# GPACConnector.net
KiCad netlist of a schematic drawn in Altium Designer
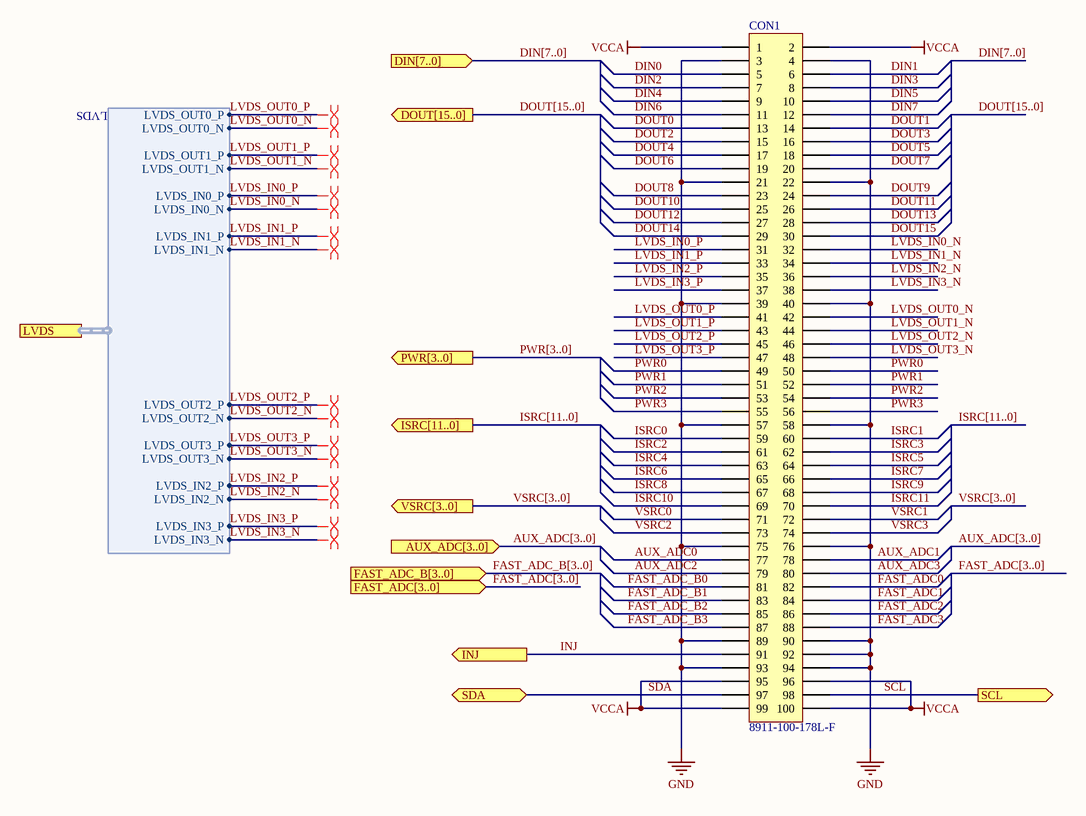
[diagram p0: GPACConnector.SchDoc]

(export (version "E")
  (design (tool "Eeschema 10.0.6"))
  (components
    (comp (ref "CON1")
      (value "-")
      (footprint "KEL 8911-100-178L-F, PLUG")
      (description "KEL 8911 100 pin board to board connector")
      (fields (field (name "TYPE_1") "8911-100-178L-F") (field (name "PUBLISHER") "Silab J.S."))
      (libsource (lib "Silab_Lib") (part "CON KEL 8911, male"))
    )
  )
  (nets
    (net (code "2") (name "/AUX_ADC0") (class "Default")
      (node (ref "CON1") (pin "77") (pinfunction "77_77") (pintype "passive"))
    )
    (net (code "3") (name "/AUX_ADC1") (class "Default")
      (node (ref "CON1") (pin "78") (pinfunction "78_78") (pintype "passive"))
    )
    (net (code "4") (name "/AUX_ADC2") (class "Default")
      (node (ref "CON1") (pin "79") (pinfunction "79_79") (pintype "passive"))
    )
    (net (code "5") (name "/AUX_ADC3") (class "Default")
      (node (ref "CON1") (pin "80") (pinfunction "80_80") (pintype "passive"))
    )
    (net (code "7") (name "/DIN0") (class "Default")
      (node (ref "CON1") (pin "5") (pinfunction "5_5") (pintype "passive"))
    )
    (net (code "8") (name "/DIN1") (class "Default")
      (node (ref "CON1") (pin "6") (pinfunction "6_6") (pintype "passive"))
    )
    (net (code "9") (name "/DIN2") (class "Default")
      (node (ref "CON1") (pin "7") (pinfunction "7_7") (pintype "passive"))
    )
    (net (code "10") (name "/DIN3") (class "Default")
      (node (ref "CON1") (pin "8") (pinfunction "8_8") (pintype "passive"))
    )
    (net (code "11") (name "/DIN4") (class "Default")
      (node (ref "CON1") (pin "9") (pinfunction "9_9") (pintype "passive"))
    )
    (net (code "12") (name "/DIN5") (class "Default")
      (node (ref "CON1") (pin "10") (pinfunction "10_10") (pintype "passive"))
    )
    (net (code "13") (name "/DIN6") (class "Default")
      (node (ref "CON1") (pin "11") (pinfunction "11_11") (pintype "passive"))
    )
    (net (code "14") (name "/DIN7") (class "Default")
      (node (ref "CON1") (pin "12") (pinfunction "12_12") (pintype "passive"))
    )
    (net (code "16") (name "/DOUT0") (class "Default")
      (node (ref "CON1") (pin "13") (pinfunction "13_13") (pintype "passive"))
    )
    (net (code "17") (name "/DOUT1") (class "Default")
      (node (ref "CON1") (pin "14") (pinfunction "14_14") (pintype "passive"))
    )
    (net (code "18") (name "/DOUT2") (class "Default")
      (node (ref "CON1") (pin "15") (pinfunction "15_15") (pintype "passive"))
    )
    (net (code "19") (name "/DOUT3") (class "Default")
      (node (ref "CON1") (pin "16") (pinfunction "16_16") (pintype "passive"))
    )
    (net (code "20") (name "/DOUT4") (class "Default")
      (node (ref "CON1") (pin "17") (pinfunction "17_17") (pintype "passive"))
    )
    (net (code "21") (name "/DOUT5") (class "Default")
      (node (ref "CON1") (pin "18") (pinfunction "18_18") (pintype "passive"))
    )
    (net (code "22") (name "/DOUT6") (class "Default")
      (node (ref "CON1") (pin "19") (pinfunction "19_19") (pintype "passive"))
    )
    (net (code "23") (name "/DOUT7") (class "Default")
      (node (ref "CON1") (pin "20") (pinfunction "20_20") (pintype "passive"))
    )
    (net (code "24") (name "/DOUT8") (class "Default")
      (node (ref "CON1") (pin "23") (pinfunction "23_23") (pintype "passive"))
    )
    (net (code "25") (name "/DOUT9") (class "Default")
      (node (ref "CON1") (pin "24") (pinfunction "24_24") (pintype "passive"))
    )
    (net (code "26") (name "/DOUT10") (class "Default")
      (node (ref "CON1") (pin "25") (pinfunction "25_25") (pintype "passive"))
    )
    (net (code "27") (name "/DOUT11") (class "Default")
      (node (ref "CON1") (pin "26") (pinfunction "26_26") (pintype "passive"))
    )
    (net (code "28") (name "/DOUT12") (class "Default")
      (node (ref "CON1") (pin "27") (pinfunction "27_27") (pintype "passive"))
    )
    (net (code "29") (name "/DOUT13") (class "Default")
      (node (ref "CON1") (pin "28") (pinfunction "28_28") (pintype "passive"))
    )
    (net (code "30") (name "/DOUT14") (class "Default")
      (node (ref "CON1") (pin "29") (pinfunction "29_29") (pintype "passive"))
    )
    (net (code "31") (name "/DOUT15") (class "Default")
      (node (ref "CON1") (pin "30") (pinfunction "30_30") (pintype "passive"))
    )
    (net (code "33") (name "/FAST_ADC0") (class "Default")
      (node (ref "CON1") (pin "82") (pinfunction "82_82") (pintype "passive"))
    )
    (net (code "34") (name "/FAST_ADC1") (class "Default")
      (node (ref "CON1") (pin "84") (pinfunction "84_84") (pintype "passive"))
    )
    (net (code "35") (name "/FAST_ADC2") (class "Default")
      (node (ref "CON1") (pin "86") (pinfunction "86_86") (pintype "passive"))
    )
    (net (code "36") (name "/FAST_ADC3") (class "Default")
      (node (ref "CON1") (pin "88") (pinfunction "88_88") (pintype "passive"))
    )
    (net (code "38") (name "/FAST_ADC_B0") (class "Default")
      (node (ref "CON1") (pin "81") (pinfunction "81_81") (pintype "passive"))
    )
    (net (code "39") (name "/FAST_ADC_B1") (class "Default")
      (node (ref "CON1") (pin "83") (pinfunction "83_83") (pintype "passive"))
    )
    (net (code "40") (name "/FAST_ADC_B2") (class "Default")
      (node (ref "CON1") (pin "85") (pinfunction "85_85") (pintype "passive"))
    )
    (net (code "41") (name "/FAST_ADC_B3") (class "Default")
      (node (ref "CON1") (pin "87") (pinfunction "87_87") (pintype "passive"))
    )
    (net (code "43") (name "/INJ") (class "Default")
      (node (ref "CON1") (pin "91") (pinfunction "91_91") (pintype "passive"))
    )
    (net (code "44") (name "/ISRC0") (class "Default")
      (node (ref "CON1") (pin "59") (pinfunction "59_59") (pintype "passive"))
    )
    (net (code "45") (name "/ISRC1") (class "Default")
      (node (ref "CON1") (pin "60") (pinfunction "60_60") (pintype "passive"))
    )
    (net (code "46") (name "/ISRC2") (class "Default")
      (node (ref "CON1") (pin "61") (pinfunction "61_61") (pintype "passive"))
    )
    (net (code "47") (name "/ISRC3") (class "Default")
      (node (ref "CON1") (pin "62") (pinfunction "62_62") (pintype "passive"))
    )
    (net (code "48") (name "/ISRC4") (class "Default")
      (node (ref "CON1") (pin "63") (pinfunction "63_63") (pintype "passive"))
    )
    (net (code "49") (name "/ISRC5") (class "Default")
      (node (ref "CON1") (pin "64") (pinfunction "64_64") (pintype "passive"))
    )
    (net (code "50") (name "/ISRC6") (class "Default")
      (node (ref "CON1") (pin "65") (pinfunction "65_65") (pintype "passive"))
    )
    (net (code "51") (name "/ISRC7") (class "Default")
      (node (ref "CON1") (pin "66") (pinfunction "66_66") (pintype "passive"))
    )
    (net (code "52") (name "/ISRC8") (class "Default")
      (node (ref "CON1") (pin "67") (pinfunction "67_67") (pintype "passive"))
    )
    (net (code "53") (name "/ISRC9") (class "Default")
      (node (ref "CON1") (pin "68") (pinfunction "68_68") (pintype "passive"))
    )
    (net (code "54") (name "/ISRC10") (class "Default")
      (node (ref "CON1") (pin "69") (pinfunction "69_69") (pintype "passive"))
    )
    (net (code "55") (name "/ISRC11") (class "Default")
      (node (ref "CON1") (pin "70") (pinfunction "70_70") (pintype "passive"))
    )
    (net (code "57") (name "/LVDS_IN0_N") (class "Default")
      (node (ref "CON1") (pin "32") (pinfunction "32_32") (pintype "passive"))
    )
    (net (code "58") (name "/LVDS_IN0_P") (class "Default")
      (node (ref "CON1") (pin "31") (pinfunction "31_31") (pintype "passive"))
    )
    (net (code "59") (name "/LVDS_IN1_N") (class "Default")
      (node (ref "CON1") (pin "34") (pinfunction "34_34") (pintype "passive"))
    )
    (net (code "60") (name "/LVDS_IN1_P") (class "Default")
      (node (ref "CON1") (pin "33") (pinfunction "33_33") (pintype "passive"))
    )
    (net (code "61") (name "/LVDS_IN2_N") (class "Default")
      (node (ref "CON1") (pin "36") (pinfunction "36_36") (pintype "passive"))
    )
    (net (code "62") (name "/LVDS_IN2_P") (class "Default")
      (node (ref "CON1") (pin "35") (pinfunction "35_35") (pintype "passive"))
    )
    (net (code "63") (name "/LVDS_IN3_N") (class "Default")
      (node (ref "CON1") (pin "38") (pinfunction "38_38") (pintype "passive"))
    )
    (net (code "64") (name "/LVDS_IN3_P") (class "Default")
      (node (ref "CON1") (pin "37") (pinfunction "37_37") (pintype "passive"))
    )
    (net (code "65") (name "/LVDS_OUT0_N") (class "Default")
      (node (ref "CON1") (pin "42") (pinfunction "42_42") (pintype "passive"))
    )
    (net (code "66") (name "/LVDS_OUT0_P") (class "Default")
      (node (ref "CON1") (pin "41") (pinfunction "41_41") (pintype "passive"))
    )
    (net (code "67") (name "/LVDS_OUT1_N") (class "Default")
      (node (ref "CON1") (pin "44") (pinfunction "44_44") (pintype "passive"))
    )
    (net (code "68") (name "/LVDS_OUT1_P") (class "Default")
      (node (ref "CON1") (pin "43") (pinfunction "43_43") (pintype "passive"))
    )
    (net (code "69") (name "/LVDS_OUT2_N") (class "Default")
      (node (ref "CON1") (pin "46") (pinfunction "46_46") (pintype "passive"))
    )
    (net (code "70") (name "/LVDS_OUT2_P") (class "Default")
      (node (ref "CON1") (pin "45") (pinfunction "45_45") (pintype "passive"))
    )
    (net (code "71") (name "/LVDS_OUT3_N") (class "Default")
      (node (ref "CON1") (pin "48") (pinfunction "48_48") (pintype "passive"))
    )
    (net (code "72") (name "/LVDS_OUT3_P") (class "Default")
      (node (ref "CON1") (pin "47") (pinfunction "47_47") (pintype "passive"))
    )
    (net (code "73") (name "/PWR0") (class "Default")
      (node (ref "CON1") (pin "49") (pinfunction "49_49") (pintype "passive"))
      (node (ref "CON1") (pin "50") (pinfunction "50_50") (pintype "passive"))
    )
    (net (code "74") (name "/PWR1") (class "Default")
      (node (ref "CON1") (pin "51") (pinfunction "51_51") (pintype "passive"))
      (node (ref "CON1") (pin "52") (pinfunction "52_52") (pintype "passive"))
    )
    (net (code "75") (name "/PWR2") (class "Default")
      (node (ref "CON1") (pin "53") (pinfunction "53_53") (pintype "passive"))
      (node (ref "CON1") (pin "54") (pinfunction "54_54") (pintype "passive"))
    )
    (net (code "76") (name "/PWR3") (class "Default")
      (node (ref "CON1") (pin "55") (pinfunction "55_55") (pintype "passive"))
      (node (ref "CON1") (pin "56") (pinfunction "56_56") (pintype "passive"))
    )
    (net (code "78") (name "/SCL") (class "Default")
      (node (ref "CON1") (pin "98") (pinfunction "98_98") (pintype "passive"))
    )
    (net (code "79") (name "/SDA") (class "Default")
      (node (ref "CON1") (pin "97") (pinfunction "97_97") (pintype "passive"))
    )
    (net (code "80") (name "/VSRC0") (class "Default")
      (node (ref "CON1") (pin "71") (pinfunction "71_71") (pintype "passive"))
    )
    (net (code "81") (name "/VSRC1") (class "Default")
      (node (ref "CON1") (pin "72") (pinfunction "72_72") (pintype "passive"))
    )
    (net (code "82") (name "/VSRC2") (class "Default")
      (node (ref "CON1") (pin "73") (pinfunction "73_73") (pintype "passive"))
    )
    (net (code "83") (name "/VSRC3") (class "Default")
      (node (ref "CON1") (pin "74") (pinfunction "74_74") (pintype "passive"))
    )
    (net (code "86") (name "GND") (class "Default")
      (node (ref "CON1") (pin "21") (pinfunction "21_21") (pintype "passive"))
      (node (ref "CON1") (pin "22") (pinfunction "22_22") (pintype "passive"))
      (node (ref "CON1") (pin "3") (pinfunction "3_3") (pintype "passive"))
      (node (ref "CON1") (pin "39") (pinfunction "39_39") (pintype "passive"))
      (node (ref "CON1") (pin "4") (pinfunction "4_4") (pintype "passive"))
      (node (ref "CON1") (pin "40") (pinfunction "40_40") (pintype "passive"))
      (node (ref "CON1") (pin "57") (pinfunction "57_57") (pintype "passive"))
      (node (ref "CON1") (pin "58") (pinfunction "58_58") (pintype "passive"))
      (node (ref "CON1") (pin "75") (pinfunction "75_75") (pintype "passive"))
      (node (ref "CON1") (pin "76") (pinfunction "76_76") (pintype "passive"))
      (node (ref "CON1") (pin "89") (pinfunction "89_89") (pintype "passive"))
      (node (ref "CON1") (pin "90") (pinfunction "90_90") (pintype "passive"))
      (node (ref "CON1") (pin "92") (pinfunction "92_92") (pintype "passive"))
      (node (ref "CON1") (pin "93") (pinfunction "93_93") (pintype "passive"))
      (node (ref "CON1") (pin "94") (pinfunction "94_94") (pintype "passive"))
    )
    (net (code "87") (name "VCCA") (class "Default")
      (node (ref "CON1") (pin "1") (pinfunction "1_1") (pintype "passive"))
      (node (ref "CON1") (pin "100") (pinfunction "100_100") (pintype "passive"))
      (node (ref "CON1") (pin "2") (pinfunction "2_2") (pintype "passive"))
      (node (ref "CON1") (pin "95") (pinfunction "95_95") (pintype "passive"))
      (node (ref "CON1") (pin "96") (pinfunction "96_96") (pintype "passive"))
      (node (ref "CON1") (pin "99") (pinfunction "99_99") (pintype "passive"))
    )
  )
)
